# Att_steet_2.net
KiCad netlist of a schematic drawn in Altium Designer
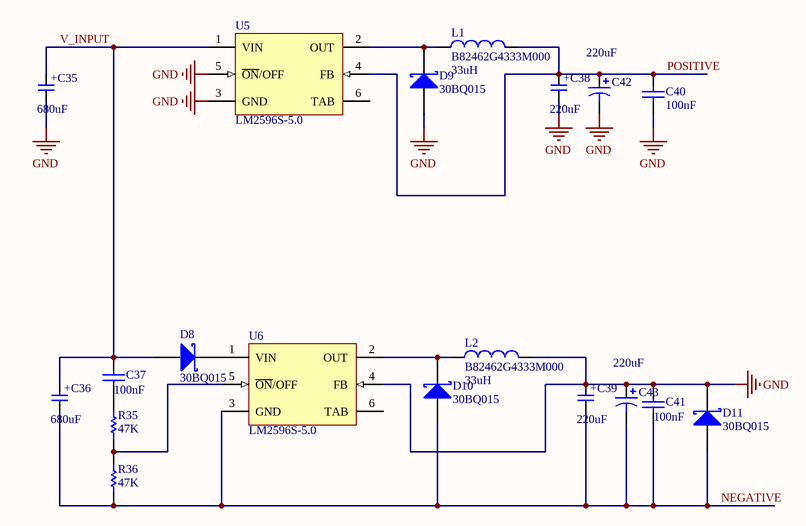
[diagram p0: Att_steet_2.SchDoc]

(export (version "E")
  (design (tool "Eeschema 10.0.6"))
  (components
    (comp (ref "C35")
      (value "680uF")
      (footprint "Scope:H13")
      (fields (field (name "MANUFACTURER") "Panasonic") (field (name "Comment") "Cap"))
      (libsource (lib "Scope") (part "Lyt Cap"))
    )
    (comp (ref "C36")
      (value "680uF")
      (footprint "Scope:H13")
      (fields (field (name "MANUFACTURER") "Panasonic") (field (name "Comment") "Cap"))
      (libsource (lib "Scope") (part "Lyt Cap"))
    )
    (comp (ref "C37")
      (value "100nF")
      (footprint "0805")
      (description "Ceramic Chip Capacitor - Standard")
      (fields (field (name "Comment") "C0805") (field (name "PUBLISHER") "Altium Limited"))
      (libsource (lib "KEMET Chip Capacitor") (part "C0805"))
    )
    (comp (ref "C38")
      (value "220uF")
      (footprint "Scope:H13")
      (fields (field (name "MANUFACTURER") "Panasonic") (field (name "Comment") "Cap"))
      (libsource (lib "Scope") (part "Lyt Cap"))
    )
    (comp (ref "C39")
      (value "220uF")
      (footprint "Scope:H13")
      (fields (field (name "MANUFACTURER") "Panasonic") (field (name "Comment") "Cap"))
      (libsource (lib "Scope") (part "Lyt Cap"))
    )
    (comp (ref "C40")
      (value "100nF")
      (footprint "0805")
      (description "Ceramic Chip Capacitor - Standard")
      (fields (field (name "Comment") "C0805") (field (name "PUBLISHER") "Altium Limited"))
      (libsource (lib "KEMET Chip Capacitor") (part "C0805"))
    )
    (comp (ref "C41")
      (value "100nF")
      (footprint "0805")
      (description "Ceramic Chip Capacitor - Standard")
      (fields (field (name "Comment") "C0805") (field (name "PUBLISHER") "Altium Limited"))
      (libsource (lib "KEMET Chip Capacitor") (part "C0805"))
    )
    (comp (ref "C42")
      (value "220uF")
      (footprint "E")
      (description "Solid Tantalum Chip Capacitor, T510 Series - Ultra-Low ESR")
      (fields (field (name "Comment") "T510E") (field (name "PUBLISHER") "Altium Limited"))
      (libsource (lib "KEMET Chip Capacitor") (part "T510E"))
    )
    (comp (ref "C43")
      (value "220uF")
      (footprint "E")
      (description "Solid Tantalum Chip Capacitor, T510 Series - Ultra-Low ESR")
      (fields (field (name "Comment") "T510E") (field (name "PUBLISHER") "Altium Limited"))
      (libsource (lib "KEMET Chip Capacitor") (part "T510E"))
    )
    (comp (ref "D8")
      (value "30BQ015")
      (footprint "SMC")
      (description "Schottky Rectifier")
      (fields (field (name "PUBLISHER") "Altium Limited"))
      (libsource (lib "IR Rectifier - Schottky") (part "30BQ015"))
    )
    (comp (ref "D9")
      (value "30BQ015")
      (footprint "SMC")
      (description "Schottky Rectifier")
      (fields (field (name "PUBLISHER") "Altium Limited"))
      (libsource (lib "IR Rectifier - Schottky") (part "30BQ015"))
    )
    (comp (ref "D10")
      (value "30BQ015")
      (footprint "SMC")
      (description "Schottky Rectifier")
      (fields (field (name "PUBLISHER") "Altium Limited"))
      (libsource (lib "IR Rectifier - Schottky") (part "30BQ015"))
    )
    (comp (ref "D11")
      (value "30BQ015")
      (footprint "SMC")
      (description "Schottky Rectifier")
      (fields (field (name "PUBLISHER") "Altium Limited"))
      (libsource (lib "IR Rectifier - Schottky") (part "30BQ015"))
    )
    (comp (ref "L1")
      (value "B82462G4333M000")
      (footprint "B82462G4")
      (description "SMT Power Inductor; Size 6.3×6.3×3.0mm, ±20% Tolerance, 33uH, 0.85A")
      (fields (field (name "ALTIUM_VALUE") "33uH") (field (name "PUBLISHER") "Altium Limited"))
      (libsource (lib "EPCOS Inductor") (part "B82462G4333M000"))
    )
    (comp (ref "L2")
      (value "B82462G4333M000")
      (footprint "B82462G4")
      (description "SMT Power Inductor; Size 6.3×6.3×3.0mm, ±20% Tolerance, 33uH, 0.85A")
      (fields (field (name "ALTIUM_VALUE") "33uH") (field (name "PUBLISHER") "Altium Limited"))
      (libsource (lib "EPCOS Inductor") (part "B82462G4333M000"))
    )
    (comp (ref "R35")
      (value "47K")
      (footprint "ERA-0805")
      (fields (field (name "Comment") "ERA6Y") (field (name "PUBLISHER") "Altium Limited"))
      (libsource (lib "Panasonic Resistor") (part "ERA6Y"))
    )
    (comp (ref "R36")
      (value "47K")
      (footprint "ERA-0805")
      (fields (field (name "Comment") "ERA6Y") (field (name "PUBLISHER") "Altium Limited"))
      (libsource (lib "Panasonic Resistor") (part "ERA6Y"))
    )
    (comp (ref "U5")
      (value "LM2596S-5.0")
      (footprint "TS5B_N")
      (description "SIMPLE SWITCHER Power Converter 150 KHz 3A Step-Down Voltage Regulator")
      (fields
        (field (name "MANUFACTURER") "National Semiconductor")
        (field (name "DIGIKEYPARTNUMBER") "LM2596S-5.0-ND")
        (field (name "PUBLISHER") "Altium Limited")
      )
      (libsource (lib "NSC Switcher") (part "LM2596S-5.0"))
    )
    (comp (ref "U6")
      (value "LM2596S-5.0")
      (footprint "TS5B_N")
      (description "SIMPLE SWITCHER Power Converter 150 KHz 3A Step-Down Voltage Regulator")
      (fields
        (field (name "MANUFACTURER") "National Semiconductor")
        (field (name "DIGIKEYPARTNUMBER") "LM2596S-5.0-ND")
        (field (name "PUBLISHER") "Altium Limited")
      )
      (libsource (lib "NSC Switcher") (part "LM2596S-5.0"))
    )
  )
  (nets
    (net (code "1") (name "/NEGATIVE") (class "Default")
      (node (ref "C36") (pin "2") (pinfunction "2_2") (pintype "passive"))
      (node (ref "C39") (pin "2") (pinfunction "2_2") (pintype "passive"))
      (node (ref "C41") (pin "1") (pinfunction "1_1") (pintype "passive"))
      (node (ref "C43") (pin "2") (pinfunction "2_2") (pintype "passive"))
      (node (ref "D10") (pin "1") (pinfunction "A_1") (pintype "passive"))
      (node (ref "D11") (pin "1") (pinfunction "A_1") (pintype "passive"))
      (node (ref "R36") (pin "2") (pinfunction "2_2") (pintype "passive"))
      (node (ref "U6") (pin "3") (pinfunction "GND_3") (pintype "power_in"))
    )
    (net (code "2") (name "/POSITIVE") (class "Default")
      (node (ref "C38") (pin "1") (pinfunction "1_1") (pintype "passive"))
      (node (ref "C40") (pin "2") (pinfunction "2_2") (pintype "passive"))
      (node (ref "C42") (pin "1") (pinfunction "1_1") (pintype "passive"))
      (node (ref "L1") (pin "2") (pinfunction "2_2") (pintype "passive"))
      (node (ref "U5") (pin "4") (pinfunction "FB_4") (pintype "input"))
    )
    (net (code "3") (name "/V_INPUT") (class "Default")
      (node (ref "C35") (pin "1") (pinfunction "1_1") (pintype "passive"))
      (node (ref "C36") (pin "1") (pinfunction "1_1") (pintype "passive"))
      (node (ref "C37") (pin "2") (pinfunction "2_2") (pintype "passive"))
      (node (ref "D8") (pin "1") (pinfunction "A_1") (pintype "passive"))
      (node (ref "U5") (pin "1") (pinfunction "VIN_1") (pintype "power_in"))
    )
    (net (code "4") (name "GND") (class "Default")
      (node (ref "C35") (pin "2") (pinfunction "2_2") (pintype "passive"))
      (node (ref "C38") (pin "2") (pinfunction "2_2") (pintype "passive"))
      (node (ref "C39") (pin "1") (pinfunction "1_1") (pintype "passive"))
      (node (ref "C40") (pin "1") (pinfunction "1_1") (pintype "passive"))
      (node (ref "C41") (pin "2") (pinfunction "2_2") (pintype "passive"))
      (node (ref "C42") (pin "2") (pinfunction "2_2") (pintype "passive"))
      (node (ref "C43") (pin "1") (pinfunction "1_1") (pintype "passive"))
      (node (ref "D11") (pin "2") (pinfunction "K_2") (pintype "passive"))
      (node (ref "D9") (pin "1") (pinfunction "A_1") (pintype "passive"))
      (node (ref "L2") (pin "2") (pinfunction "2_2") (pintype "passive"))
      (node (ref "U5") (pin "3") (pinfunction "GND_3") (pintype "power_in"))
      (node (ref "U5") (pin "5") (pinfunction "~{ON}/OFF_5") (pintype "input"))
      (node (ref "U6") (pin "4") (pinfunction "FB_4") (pintype "input"))
    )
    (net (code "5") (name "Net-(C37-Pad1)") (class "Default")
      (node (ref "C37") (pin "1") (pinfunction "1_1") (pintype "passive"))
      (node (ref "R35") (pin "1") (pinfunction "1_1") (pintype "passive"))
    )
    (net (code "6") (name "Net-(D8-K)") (class "Default")
      (node (ref "D8") (pin "2") (pinfunction "K_2") (pintype "passive"))
      (node (ref "U6") (pin "1") (pinfunction "VIN_1") (pintype "power_in"))
    )
    (net (code "7") (name "Net-(D9-K)") (class "Default")
      (node (ref "D9") (pin "2") (pinfunction "K_2") (pintype "passive"))
      (node (ref "L1") (pin "1") (pinfunction "1_1") (pintype "passive"))
      (node (ref "U5") (pin "2") (pinfunction "OUT_2") (pintype "power_in"))
    )
    (net (code "8") (name "Net-(D10-K)") (class "Default")
      (node (ref "D10") (pin "2") (pinfunction "K_2") (pintype "passive"))
      (node (ref "L2") (pin "1") (pinfunction "1_1") (pintype "passive"))
      (node (ref "U6") (pin "2") (pinfunction "OUT_2") (pintype "power_in"))
    )
    (net (code "9") (name "Net-(U6-~{ON}{slash}OFF)") (class "Default")
      (node (ref "R35") (pin "2") (pinfunction "2_2") (pintype "passive"))
      (node (ref "R36") (pin "1") (pinfunction "1_1") (pintype "passive"))
      (node (ref "U6") (pin "5") (pinfunction "~{ON}/OFF_5") (pintype "input"))
    )
    (net (code "10") (name "unconnected-(U5-TAB-Pad6)") (class "Default")
      (node (ref "U5") (pin "6") (pinfunction "TAB_6") (pintype "power_in"))
    )
    (net (code "11") (name "unconnected-(U6-TAB-Pad6)") (class "Default")
      (node (ref "U6") (pin "6") (pinfunction "TAB_6") (pintype "power_in"))
    )
  )
)
